# RILey_Schematic.net
KiCad netlist of a schematic drawn in EAGLE
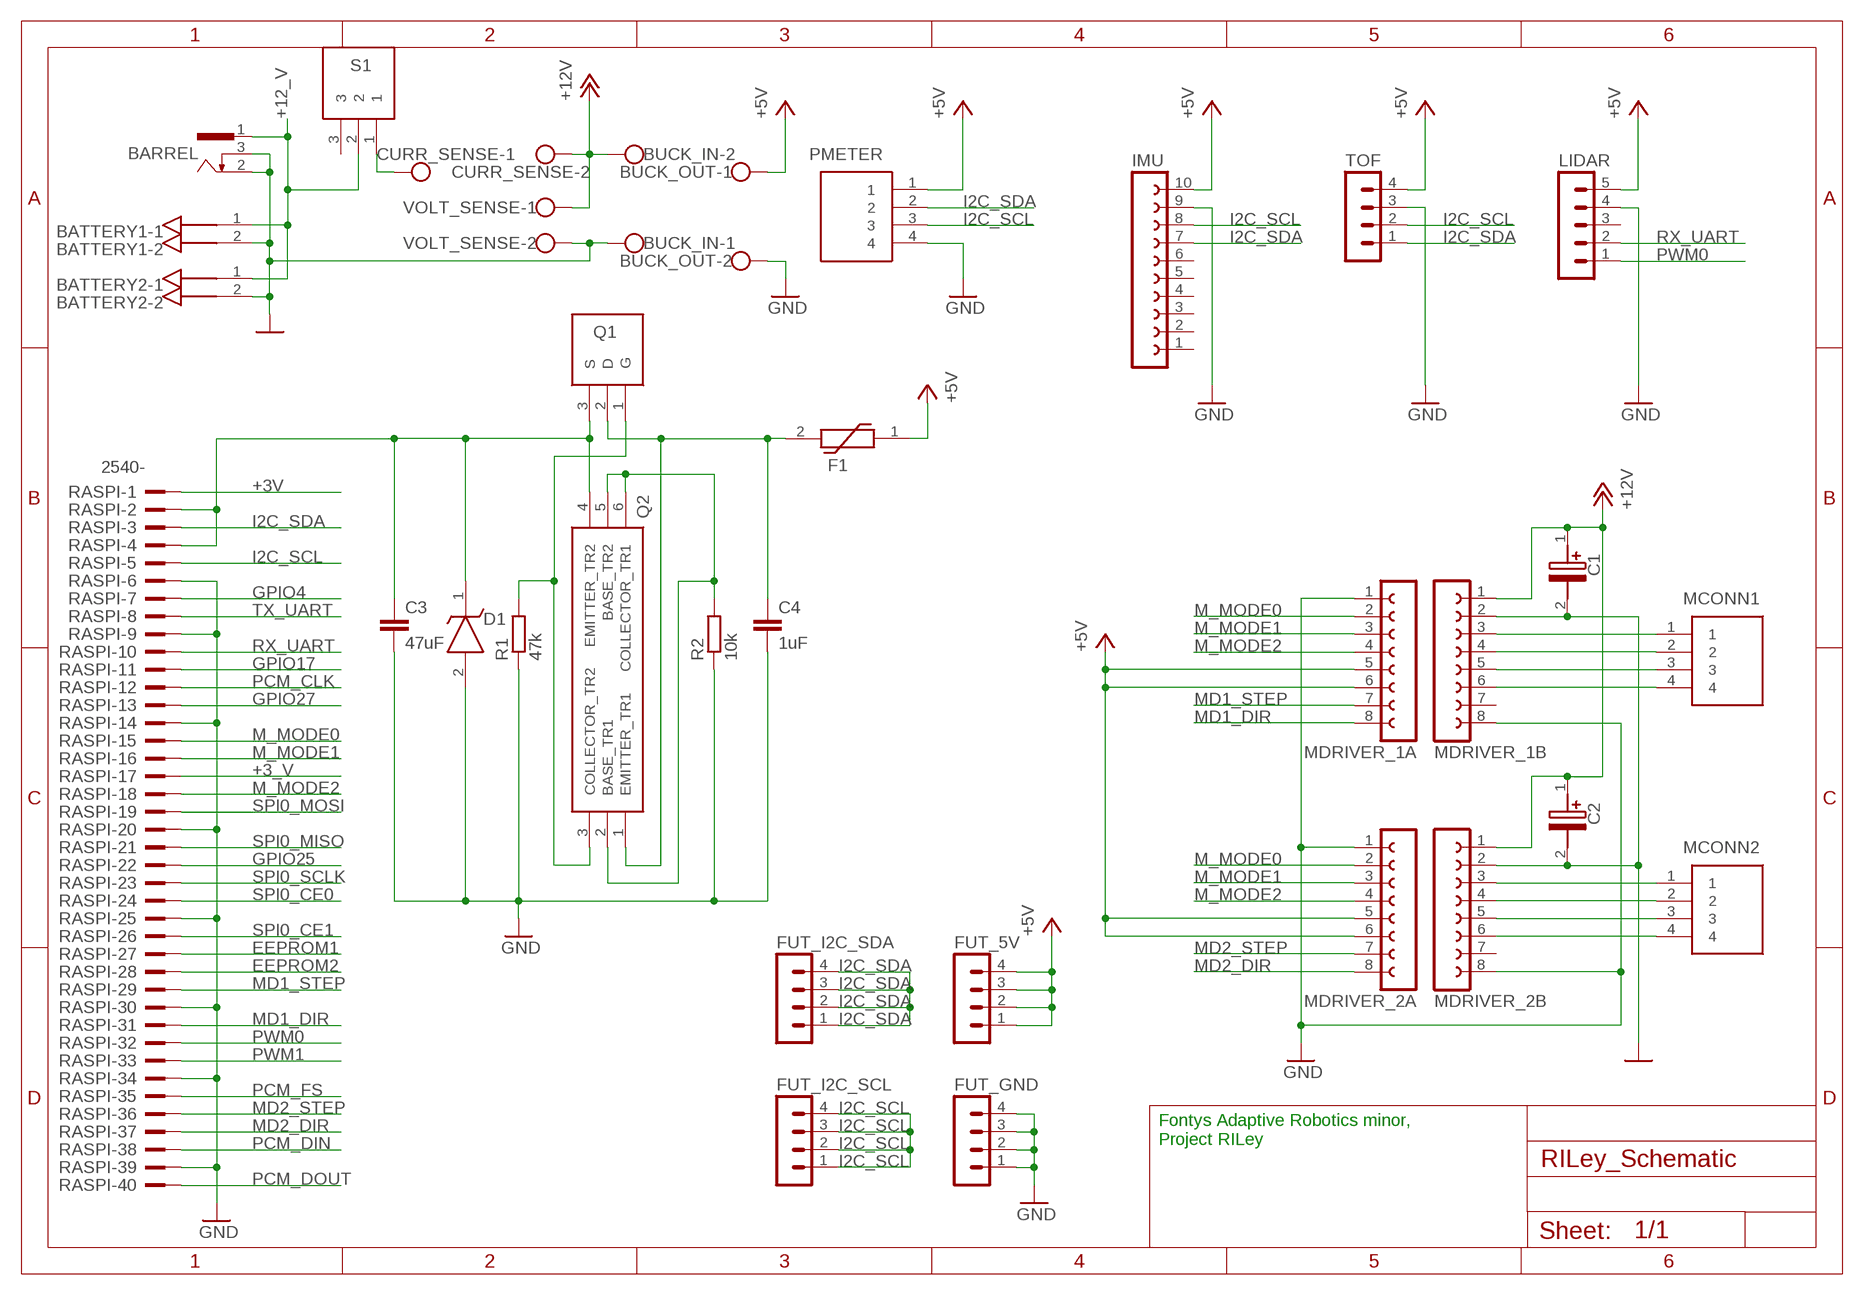
[diagram p0: schematic, sheet 1]

(export (version "E")
  (design (tool "Eeschema 10.0.6"))
  (components
    (comp (ref "BARREL")
      (value "733980-62")
      (footprint "eagle-import:733980-62")
      (libsource (lib "eagle-import") (part "73398?0-62"))
    )
    (comp (ref "BATTERY1")
      (value "0026604020")
      (footprint "eagle-import:KK41791-4020_2-PIN")
      (fields (field (name "MANUFACTURER") "Molex Inc"))
      (libsource (lib "eagle-import") (part "0026604020"))
    )
    (comp (ref "BATTERY2")
      (value "0026604020")
      (footprint "eagle-import:KK41791-4020_2-PIN")
      (fields (field (name "MANUFACTURER") "Molex Inc"))
      (libsource (lib "eagle-import") (part "0026604020"))
    )
    (comp (ref "BUCK_IN")
      (value "W237-102")
      (footprint "eagle-import:W237-102")
      (fields (field (name "MPN") "237-102"))
      (libsource (lib "eagle-import") (part "W237-102"))
    )
    (comp (ref "BUCK_OUT")
      (value "W237-102")
      (footprint "eagle-import:W237-102")
      (fields (field (name "MPN") "237-102"))
      (libsource (lib "eagle-import") (part "W237-102"))
    )
    (comp (ref "C1")
      (value "100uF")
      (footprint "eagle-import:CAPPRD250W50D655H1250")
      (fields
        (field (name "MANUFACTURER_PART_NUMBER") "UPS1E101MED")
        (field (name "RS_PART_NUMBER") "5194059P")
      )
      (libsource (lib "eagle-import") (part "UPS1E101MED"))
    )
    (comp (ref "C2")
      (value "100uF")
      (footprint "eagle-import:CAPPRD250W50D655H1250")
      (fields
        (field (name "MANUFACTURER_PART_NUMBER") "UPS1E101MED")
        (field (name "RS_PART_NUMBER") "5194059P")
      )
      (libsource (lib "eagle-import") (part "UPS1E101MED"))
    )
    (comp (ref "C3")
      (value "47uF")
      (footprint "eagle-import:C5B2.5")
      (libsource (lib "eagle-import") (part "C5/2.5"))
    )
    (comp (ref "C4")
      (value "1uF")
      (footprint "eagle-import:C2.5-3")
      (libsource (lib "eagle-import") (part "C2,5-3"))
    )
    (comp (ref "CURR_SENSE")
      (value "W237-102")
      (footprint "eagle-import:W237-102")
      (fields (field (name "MPN") "237-102"))
      (libsource (lib "eagle-import") (part "W237-102"))
    )
    (comp (ref "D1")
      (value "SA5.0A-E3_54")
      (footprint "eagle-import:DIOAD1910W86L670D310")
      (fields
        (field (name "MANUFACTURER_PART_NUMBER") "SA5.0A-E3/54")
        (field (name "RS_PART_NUMBER") "6365527P")
      )
      (libsource (lib "eagle-import") (part "SA5.0A-E3_54"))
    )
    (comp (ref "F1")
      (value "PTS18126V260")
      (footprint "eagle-import:FUSC4632X90N")
      (libsource (lib "eagle-import") (part "PTS18126V260"))
    )
    (comp (ref "FUT_5V")
      (value "MA04-1")
      (footprint "eagle-import:MA04-1")
      (libsource (lib "eagle-import") (part "MA04-1"))
    )
    (comp (ref "FUT_GND")
      (value "MA04-1")
      (footprint "eagle-import:MA04-1")
      (libsource (lib "eagle-import") (part "MA04-1"))
    )
    (comp (ref "FUT_I2C_SCL")
      (value "MA04-1")
      (footprint "eagle-import:MA04-1")
      (libsource (lib "eagle-import") (part "MA04-1"))
    )
    (comp (ref "FUT_I2C_SDA")
      (value "MA04-1")
      (footprint "eagle-import:MA04-1")
      (libsource (lib "eagle-import") (part "MA04-1"))
    )
    (comp (ref "IMU")
      (value "FE10-1")
      (footprint "eagle-import:FE10")
      (libsource (lib "eagle-import") (part "FE10-1"))
    )
    (comp (ref "LIDAR")
      (value "MA05-1")
      (footprint "eagle-import:MA05-1")
      (libsource (lib "eagle-import") (part "MA05-1"))
    )
    (comp (ref "MCONN1")
      (value "B4B-XH-A_LF__SN_")
      (footprint "eagle-import:SHDR4W64P0X250_1X4_1240X575X70")
      (fields (field (name "MANUFACTURER_PART_NUMBER") "B4B-XH-A(LF)(SN)"))
      (libsource (lib "eagle-import") (part "B4B-XH-A_LF__SN_"))
    )
    (comp (ref "MCONN2")
      (value "B4B-XH-A_LF__SN_")
      (footprint "eagle-import:SHDR4W64P0X250_1X4_1240X575X70")
      (fields (field (name "MANUFACTURER_PART_NUMBER") "B4B-XH-A(LF)(SN)"))
      (libsource (lib "eagle-import") (part "B4B-XH-A_LF__SN_"))
    )
    (comp (ref "MDRIVER_1A")
      (value "FE08-1")
      (footprint "eagle-import:FE08")
      (libsource (lib "eagle-import") (part "FE08-1"))
    )
    (comp (ref "MDRIVER_1B")
      (value "FE08-1")
      (footprint "eagle-import:FE08")
      (libsource (lib "eagle-import") (part "FE08-1"))
    )
    (comp (ref "MDRIVER_2A")
      (value "FE08-1")
      (footprint "eagle-import:FE08")
      (libsource (lib "eagle-import") (part "FE08-1"))
    )
    (comp (ref "MDRIVER_2B")
      (value "FE08-1")
      (footprint "eagle-import:FE08")
      (libsource (lib "eagle-import") (part "FE08-1"))
    )
    (comp (ref "PMETER")
      (value "BLG1X4")
      (footprint "eagle-import:RHDR4W64P0X254_1X4_1066X250X86")
      (libsource (lib "eagle-import") (part "BLG1X4"))
    )
    (comp (ref "Q1")
      (value "IRF9530NPBF")
      (footprint "eagle-import:TO254P469X1042X1967-3P")
      (fields (field (name "RS_PART_NUMBER") "2509059275"))
      (libsource (lib "eagle-import") (part "IRF9530NPBF"))
    )
    (comp (ref "Q2")
      (value "BCM857BS,115")
      (footprint "eagle-import:SOT65P210X110-6N")
      (fields (field (name "RS_PART_NUMBER") "0509706"))
      (libsource (lib "eagle-import") (part "BCM857BS,115"))
    )
    (comp (ref "R1")
      (value "47k")
      (footprint "eagle-import:0207_10")
      (libsource (lib "eagle-import") (part "R-EU_0207/10"))
    )
    (comp (ref "R2")
      (value "10k")
      (footprint "eagle-import:0207_10")
      (libsource (lib "eagle-import") (part "R-EU_0207/10"))
    )
    (comp (ref "RASPI")
      (value "2540-")
      (footprint "eagle-import:PAK100_2500-40")
      (libsource (lib "eagle-import") (part "2540-"))
    )
    (comp (ref "S1")
      (value "1101M2S3CQE2")
      (footprint "eagle-import:1000-SERIES(SPDT)")
      (fields (field (name "RS_PART_NUMBER") "1617340"))
      (libsource (lib "eagle-import") (part "1101M2S3CQE2"))
    )
    (comp (ref "TOF")
      (value "MA04-1")
      (footprint "eagle-import:MA04-1")
      (libsource (lib "eagle-import") (part "MA04-1"))
    )
    (comp (ref "VOLT_SENSE")
      (value "W237-102")
      (footprint "eagle-import:W237-102")
      (fields (field (name "MPN") "237-102"))
      (libsource (lib "eagle-import") (part "W237-102"))
    )
  )
  (nets
    (net (code "1") (name "+5V") (class "Default")
      (node (ref "BUCK_OUT") (pin "1") (pinfunction "KL_1") (pintype "passive"))
      (node (ref "F1") (pin "1") (pinfunction "1_1") (pintype "bidirectional"))
      (node (ref "FUT_5V") (pin "1") (pinfunction "1_1") (pintype "passive"))
      (node (ref "FUT_5V") (pin "2") (pinfunction "2_2") (pintype "passive"))
      (node (ref "FUT_5V") (pin "3") (pinfunction "3_3") (pintype "passive"))
      (node (ref "FUT_5V") (pin "4") (pinfunction "4_4") (pintype "passive"))
      (node (ref "IMU") (pin "10") (pinfunction "10_10") (pintype "passive"))
      (node (ref "LIDAR") (pin "5") (pinfunction "5_5") (pintype "passive"))
      (node (ref "MDRIVER_1A") (pin "5") (pinfunction "5_5") (pintype "passive"))
      (node (ref "MDRIVER_1A") (pin "6") (pinfunction "6_6") (pintype "passive"))
      (node (ref "MDRIVER_2A") (pin "5") (pinfunction "5_5") (pintype "passive"))
      (node (ref "MDRIVER_2A") (pin "6") (pinfunction "6_6") (pintype "passive"))
      (node (ref "PMETER") (pin "1") (pinfunction "1_1") (pintype "bidirectional"))
      (node (ref "TOF") (pin "4") (pinfunction "4_4") (pintype "passive"))
    )
    (net (code "2") (name "+12V") (class "Default")
      (node (ref "BUCK_IN") (pin "2") (pinfunction "KL_2") (pintype "passive"))
      (node (ref "C1") (pin "1") (pinfunction "+_1") (pintype "bidirectional"))
      (node (ref "C2") (pin "1") (pinfunction "+_1") (pintype "bidirectional"))
      (node (ref "CURR_SENSE") (pin "2") (pinfunction "KL_2") (pintype "passive"))
      (node (ref "MDRIVER_1B") (pin "1") (pinfunction "1_1") (pintype "passive"))
      (node (ref "MDRIVER_2B") (pin "1") (pinfunction "1_1") (pintype "passive"))
      (node (ref "VOLT_SENSE") (pin "1") (pinfunction "KL_1") (pintype "passive"))
    )
    (net (code "3") (name "/+3V") (class "Default")
      (node (ref "RASPI") (pin "1") (pinfunction "KL_1") (pintype "passive"))
    )
    (net (code "4") (name "/+3_V") (class "Default")
      (node (ref "RASPI") (pin "17") (pinfunction "KL_17") (pintype "passive"))
    )
    (net (code "5") (name "/+12_V") (class "Default")
      (node (ref "BARREL") (pin "1") (pinfunction "1_1") (pintype "passive"))
      (node (ref "BATTERY1") (pin "1") (pinfunction "P$1_1") (pintype "bidirectional"))
      (node (ref "BATTERY2") (pin "1") (pinfunction "P$1_1") (pintype "bidirectional"))
      (node (ref "S1") (pin "2") (pinfunction "2_2") (pintype "bidirectional"))
    )
    (net (code "6") (name "/EEPROM1") (class "Default")
      (node (ref "RASPI") (pin "27") (pinfunction "KL_27") (pintype "passive"))
    )
    (net (code "7") (name "/EEPROM2") (class "Default")
      (node (ref "RASPI") (pin "28") (pinfunction "KL_28") (pintype "passive"))
    )
    (net (code "8") (name "/GPIO4") (class "Default")
      (node (ref "RASPI") (pin "7") (pinfunction "KL_7") (pintype "passive"))
    )
    (net (code "9") (name "/GPIO17") (class "Default")
      (node (ref "RASPI") (pin "11") (pinfunction "KL_11") (pintype "passive"))
    )
    (net (code "10") (name "/GPIO25") (class "Default")
      (node (ref "RASPI") (pin "22") (pinfunction "KL_22") (pintype "passive"))
    )
    (net (code "11") (name "/GPIO27") (class "Default")
      (node (ref "RASPI") (pin "13") (pinfunction "KL_13") (pintype "passive"))
    )
    (net (code "12") (name "/I2C_SCL") (class "Default")
      (node (ref "FUT_I2C_SCL") (pin "1") (pinfunction "1_1") (pintype "passive"))
      (node (ref "FUT_I2C_SCL") (pin "2") (pinfunction "2_2") (pintype "passive"))
      (node (ref "FUT_I2C_SCL") (pin "3") (pinfunction "3_3") (pintype "passive"))
      (node (ref "FUT_I2C_SCL") (pin "4") (pinfunction "4_4") (pintype "passive"))
      (node (ref "IMU") (pin "8") (pinfunction "8_8") (pintype "passive"))
      (node (ref "PMETER") (pin "3") (pinfunction "3_3") (pintype "bidirectional"))
      (node (ref "RASPI") (pin "5") (pinfunction "KL_5") (pintype "passive"))
      (node (ref "TOF") (pin "2") (pinfunction "2_2") (pintype "passive"))
    )
    (net (code "13") (name "/I2C_SDA") (class "Default")
      (node (ref "FUT_I2C_SDA") (pin "1") (pinfunction "1_1") (pintype "passive"))
      (node (ref "FUT_I2C_SDA") (pin "2") (pinfunction "2_2") (pintype "passive"))
      (node (ref "FUT_I2C_SDA") (pin "3") (pinfunction "3_3") (pintype "passive"))
      (node (ref "FUT_I2C_SDA") (pin "4") (pinfunction "4_4") (pintype "passive"))
      (node (ref "IMU") (pin "7") (pinfunction "7_7") (pintype "passive"))
      (node (ref "PMETER") (pin "2") (pinfunction "2_2") (pintype "bidirectional"))
      (node (ref "RASPI") (pin "3") (pinfunction "KL_3") (pintype "passive"))
      (node (ref "TOF") (pin "1") (pinfunction "1_1") (pintype "passive"))
    )
    (net (code "14") (name "/MD1_DIR") (class "Default")
      (node (ref "MDRIVER_1A") (pin "8") (pinfunction "8_8") (pintype "passive"))
      (node (ref "RASPI") (pin "31") (pinfunction "KL_31") (pintype "passive"))
    )
    (net (code "15") (name "/MD1_STEP") (class "Default")
      (node (ref "MDRIVER_1A") (pin "7") (pinfunction "7_7") (pintype "passive"))
      (node (ref "RASPI") (pin "29") (pinfunction "KL_29") (pintype "passive"))
    )
    (net (code "16") (name "/MD2_DIR") (class "Default")
      (node (ref "MDRIVER_2A") (pin "8") (pinfunction "8_8") (pintype "passive"))
      (node (ref "RASPI") (pin "37") (pinfunction "KL_37") (pintype "passive"))
    )
    (net (code "17") (name "/MD2_STEP") (class "Default")
      (node (ref "MDRIVER_2A") (pin "7") (pinfunction "7_7") (pintype "passive"))
      (node (ref "RASPI") (pin "36") (pinfunction "KL_36") (pintype "passive"))
    )
    (net (code "18") (name "/M_MODE0") (class "Default")
      (node (ref "MDRIVER_1A") (pin "2") (pinfunction "2_2") (pintype "passive"))
      (node (ref "MDRIVER_2A") (pin "2") (pinfunction "2_2") (pintype "passive"))
      (node (ref "RASPI") (pin "15") (pinfunction "KL_15") (pintype "passive"))
    )
    (net (code "19") (name "/M_MODE1") (class "Default")
      (node (ref "MDRIVER_1A") (pin "3") (pinfunction "3_3") (pintype "passive"))
      (node (ref "MDRIVER_2A") (pin "3") (pinfunction "3_3") (pintype "passive"))
      (node (ref "RASPI") (pin "16") (pinfunction "KL_16") (pintype "passive"))
    )
    (net (code "20") (name "/M_MODE2") (class "Default")
      (node (ref "MDRIVER_1A") (pin "4") (pinfunction "4_4") (pintype "passive"))
      (node (ref "MDRIVER_2A") (pin "4") (pinfunction "4_4") (pintype "passive"))
      (node (ref "RASPI") (pin "18") (pinfunction "KL_18") (pintype "passive"))
    )
    (net (code "21") (name "/PCM_CLK") (class "Default")
      (node (ref "RASPI") (pin "12") (pinfunction "KL_12") (pintype "passive"))
    )
    (net (code "22") (name "/PCM_DIN") (class "Default")
      (node (ref "RASPI") (pin "38") (pinfunction "KL_38") (pintype "passive"))
    )
    (net (code "23") (name "/PCM_DOUT") (class "Default")
      (node (ref "RASPI") (pin "40") (pinfunction "KL_40") (pintype "passive"))
    )
    (net (code "24") (name "/PCM_FS") (class "Default")
      (node (ref "RASPI") (pin "35") (pinfunction "KL_35") (pintype "passive"))
    )
    (net (code "25") (name "/PWM0") (class "Default")
      (node (ref "LIDAR") (pin "1") (pinfunction "1_1") (pintype "passive"))
      (node (ref "RASPI") (pin "32") (pinfunction "KL_32") (pintype "passive"))
    )
    (net (code "26") (name "/PWM1") (class "Default")
      (node (ref "RASPI") (pin "33") (pinfunction "KL_33") (pintype "passive"))
    )
    (net (code "27") (name "/RX_UART") (class "Default")
      (node (ref "LIDAR") (pin "2") (pinfunction "2_2") (pintype "passive"))
      (node (ref "RASPI") (pin "10") (pinfunction "KL_10") (pintype "passive"))
    )
    (net (code "28") (name "/SPI0_CE0") (class "Default")
      (node (ref "RASPI") (pin "24") (pinfunction "KL_24") (pintype "passive"))
    )
    (net (code "29") (name "/SPI0_CE1") (class "Default")
      (node (ref "RASPI") (pin "26") (pinfunction "KL_26") (pintype "passive"))
    )
    (net (code "30") (name "/SPI0_MISO") (class "Default")
      (node (ref "RASPI") (pin "21") (pinfunction "KL_21") (pintype "passive"))
    )
    (net (code "31") (name "/SPI0_MOSI") (class "Default")
      (node (ref "RASPI") (pin "19") (pinfunction "KL_19") (pintype "passive"))
    )
    (net (code "32") (name "/SPI0_SCLK") (class "Default")
      (node (ref "RASPI") (pin "23") (pinfunction "KL_23") (pintype "passive"))
    )
    (net (code "33") (name "/TX_UART") (class "Default")
      (node (ref "RASPI") (pin "8") (pinfunction "KL_8") (pintype "passive"))
    )
    (net (code "34") (name "0V") (class "Default")
      (node (ref "BARREL") (pin "2") (pinfunction "2_2") (pintype "passive"))
      (node (ref "BARREL") (pin "3") (pinfunction "3_3") (pintype "passive"))
      (node (ref "BATTERY1") (pin "2") (pinfunction "P$1_2") (pintype "bidirectional"))
      (node (ref "BATTERY2") (pin "2") (pinfunction "P$1_2") (pintype "bidirectional"))
      (node (ref "BUCK_IN") (pin "1") (pinfunction "KL_1") (pintype "passive"))
      (node (ref "C1") (pin "2") (pinfunction "-_2") (pintype "bidirectional"))
      (node (ref "C2") (pin "2") (pinfunction "-_2") (pintype "bidirectional"))
      (node (ref "MDRIVER_1B") (pin "2") (pinfunction "2_2") (pintype "passive"))
      (node (ref "MDRIVER_2B") (pin "2") (pinfunction "2_2") (pintype "passive"))
      (node (ref "VOLT_SENSE") (pin "2") (pinfunction "KL_2") (pintype "passive"))
    )
    (net (code "35") (name "GND") (class "Default")
      (node (ref "BUCK_OUT") (pin "2") (pinfunction "KL_2") (pintype "passive"))
      (node (ref "C3") (pin "2") (pinfunction "2_2") (pintype "passive"))
      (node (ref "C4") (pin "2") (pinfunction "2_2") (pintype "passive"))
      (node (ref "D1") (pin "2") (pinfunction "A_2") (pintype "bidirectional"))
      (node (ref "FUT_GND") (pin "1") (pinfunction "1_1") (pintype "passive"))
      (node (ref "FUT_GND") (pin "2") (pinfunction "2_2") (pintype "passive"))
      (node (ref "FUT_GND") (pin "3") (pinfunction "3_3") (pintype "passive"))
      (node (ref "FUT_GND") (pin "4") (pinfunction "4_4") (pintype "passive"))
      (node (ref "IMU") (pin "9") (pinfunction "9_9") (pintype "passive"))
      (node (ref "LIDAR") (pin "4") (pinfunction "4_4") (pintype "passive"))
      (node (ref "MDRIVER_1A") (pin "1") (pinfunction "1_1") (pintype "passive"))
      (node (ref "MDRIVER_1B") (pin "8") (pinfunction "8_8") (pintype "passive"))
      (node (ref "MDRIVER_2A") (pin "1") (pinfunction "1_1") (pintype "passive"))
      (node (ref "MDRIVER_2B") (pin "8") (pinfunction "8_8") (pintype "passive"))
      (node (ref "PMETER") (pin "4") (pinfunction "4_4") (pintype "bidirectional"))
      (node (ref "R1") (pin "1") (pinfunction "1_1") (pintype "passive"))
      (node (ref "R2") (pin "1") (pinfunction "1_1") (pintype "passive"))
      (node (ref "RASPI") (pin "14") (pinfunction "KL_14") (pintype "passive"))
      (node (ref "RASPI") (pin "20") (pinfunction "KL_20") (pintype "passive"))
      (node (ref "RASPI") (pin "25") (pinfunction "KL_25") (pintype "passive"))
      (node (ref "RASPI") (pin "30") (pinfunction "KL_30") (pintype "passive"))
      (node (ref "RASPI") (pin "34") (pinfunction "KL_34") (pintype "passive"))
      (node (ref "RASPI") (pin "39") (pinfunction "KL_39") (pintype "passive"))
      (node (ref "RASPI") (pin "6") (pinfunction "KL_6") (pintype "passive"))
      (node (ref "RASPI") (pin "9") (pinfunction "KL_9") (pintype "passive"))
      (node (ref "TOF") (pin "3") (pinfunction "3_3") (pintype "passive"))
    )
    (net (code "36") (name "Net-(CURR_SENSEA-KL)") (class "Default")
      (node (ref "CURR_SENSE") (pin "1") (pinfunction "KL_1") (pintype "passive"))
      (node (ref "S1") (pin "1") (pinfunction "1_1") (pintype "bidirectional"))
    )
    (net (code "37") (name "Net-(D1-K)") (class "Default")
      (node (ref "C3") (pin "1") (pinfunction "1_1") (pintype "passive"))
      (node (ref "D1") (pin "1") (pinfunction "K_1") (pintype "bidirectional"))
      (node (ref "Q1") (pin "3") (pinfunction "S_3") (pintype "bidirectional"))
      (node (ref "Q2") (pin "4") (pinfunction "EMITTER_TR2_4") (pintype "bidirectional"))
      (node (ref "RASPI") (pin "2") (pinfunction "KL_2") (pintype "passive"))
      (node (ref "RASPI") (pin "4") (pinfunction "KL_4") (pintype "passive"))
    )
    (net (code "38") (name "Net-(MCONN1-Pad1)") (class "Default")
      (node (ref "MCONN1") (pin "1") (pinfunction "1_1") (pintype "bidirectional"))
      (node (ref "MDRIVER_1B") (pin "3") (pinfunction "3_3") (pintype "passive"))
    )
    (net (code "39") (name "Net-(MCONN1-Pad2)") (class "Default")
      (node (ref "MCONN1") (pin "2") (pinfunction "2_2") (pintype "bidirectional"))
      (node (ref "MDRIVER_1B") (pin "4") (pinfunction "4_4") (pintype "passive"))
    )
    (net (code "40") (name "Net-(MCONN1-Pad3)") (class "Default")
      (node (ref "MCONN1") (pin "3") (pinfunction "3_3") (pintype "bidirectional"))
      (node (ref "MDRIVER_1B") (pin "5") (pinfunction "5_5") (pintype "passive"))
    )
    (net (code "41") (name "Net-(MCONN1-Pad4)") (class "Default")
      (node (ref "MCONN1") (pin "4") (pinfunction "4_4") (pintype "bidirectional"))
      (node (ref "MDRIVER_1B") (pin "6") (pinfunction "6_6") (pintype "passive"))
    )
    (net (code "42") (name "Net-(MCONN2-Pad1)") (class "Default")
      (node (ref "MCONN2") (pin "1") (pinfunction "1_1") (pintype "bidirectional"))
      (node (ref "MDRIVER_2B") (pin "3") (pinfunction "3_3") (pintype "passive"))
    )
    (net (code "43") (name "Net-(MCONN2-Pad2)") (class "Default")
      (node (ref "MCONN2") (pin "2") (pinfunction "2_2") (pintype "bidirectional"))
      (node (ref "MDRIVER_2B") (pin "4") (pinfunction "4_4") (pintype "passive"))
    )
    (net (code "44") (name "Net-(MCONN2-Pad3)") (class "Default")
      (node (ref "MCONN2") (pin "3") (pinfunction "3_3") (pintype "bidirectional"))
      (node (ref "MDRIVER_2B") (pin "5") (pinfunction "5_5") (pintype "passive"))
    )
    (net (code "45") (name "Net-(MCONN2-Pad4)") (class "Default")
      (node (ref "MCONN2") (pin "4") (pinfunction "4_4") (pintype "bidirectional"))
      (node (ref "MDRIVER_2B") (pin "6") (pinfunction "6_6") (pintype "passive"))
    )
    (net (code "46") (name "Net-(Q1-D)") (class "Default")
      (node (ref "C4") (pin "1") (pinfunction "1_1") (pintype "passive"))
      (node (ref "F1") (pin "2") (pinfunction "2_2") (pintype "bidirectional"))
      (node (ref "Q1") (pin "2") (pinfunction "D_2") (pintype "bidirectional"))
      (node (ref "Q2") (pin "1") (pinfunction "EMITTER_TR1_1") (pintype "bidirectional"))
    )
    (net (code "47") (name "Net-(Q1-G)") (class "Default")
      (node (ref "Q1") (pin "1") (pinfunction "G_1") (pintype "bidirectional"))
      (node (ref "Q2") (pin "3") (pinfunction "COLLECTOR_TR2_3") (pintype "bidirectional"))
      (node (ref "R1") (pin "2") (pinfunction "2_2") (pintype "passive"))
    )
    (net (code "48") (name "Net-(Q2-BASE_TR1)") (class "Default")
      (node (ref "Q2") (pin "2") (pinfunction "BASE_TR1_2") (pintype "bidirectional"))
      (node (ref "Q2") (pin "5") (pinfunction "BASE_TR2_5") (pintype "bidirectional"))
      (node (ref "Q2") (pin "6") (pinfunction "COLLECTOR_TR1_6") (pintype "bidirectional"))
      (node (ref "R2") (pin "2") (pinfunction "2_2") (pintype "passive"))
    )
    (net (code "49") (name "unconnected-(IMU-Pad1)") (class "Default")
      (node (ref "IMU") (pin "1") (pinfunction "1_1") (pintype "passive"))
    )
    (net (code "50") (name "unconnected-(IMU-Pad2)") (class "Default")
      (node (ref "IMU") (pin "2") (pinfunction "2_2") (pintype "passive"))
    )
    (net (code "51") (name "unconnected-(IMU-Pad3)") (class "Default")
      (node (ref "IMU") (pin "3") (pinfunction "3_3") (pintype "passive"))
    )
    (net (code "52") (name "unconnected-(IMU-Pad4)") (class "Default")
      (node (ref "IMU") (pin "4") (pinfunction "4_4") (pintype "passive"))
    )
    (net (code "53") (name "unconnected-(IMU-Pad5)") (class "Default")
      (node (ref "IMU") (pin "5") (pinfunction "5_5") (pintype "passive"))
    )
    (net (code "54") (name "unconnected-(IMU-Pad6)") (class "Default")
      (node (ref "IMU") (pin "6") (pinfunction "6_6") (pintype "passive"))
    )
    (net (code "55") (name "unconnected-(LIDAR-Pad3)") (class "Default")
      (node (ref "LIDAR") (pin "3") (pinfunction "3_3") (pintype "passive"))
    )
    (net (code "56") (name "unconnected-(MDRIVER_1B-Pad7)") (class "Default")
      (node (ref "MDRIVER_1B") (pin "7") (pinfunction "7_7") (pintype "passive"))
    )
    (net (code "57") (name "unconnected-(MDRIVER_2B-Pad7)") (class "Default")
      (node (ref "MDRIVER_2B") (pin "7") (pinfunction "7_7") (pintype "passive"))
    )
    (net (code "58") (name "unconnected-(S1-Pad3)") (class "Default")
      (node (ref "S1") (pin "3") (pinfunction "3_3") (pintype "bidirectional"))
    )
  )
)
